# LED_Driver.net
KiCad netlist of a schematic drawn in Altium Designer
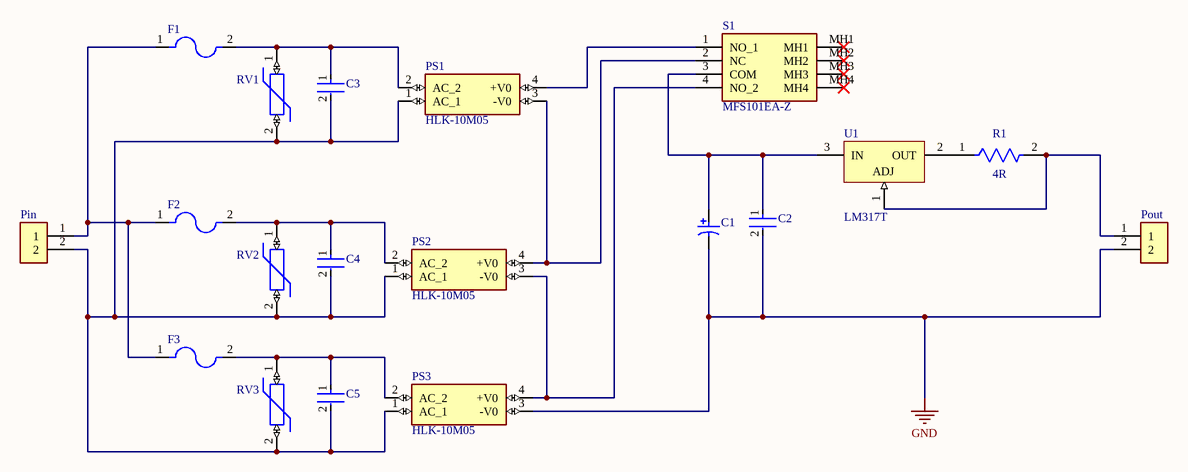
[diagram p0: LED_Driver.SchDoc]

(export (version "E")
  (design (tool "Eeschema 10.0.6"))
  (components
    (comp (ref "C1")
      (value "ECA-1VM221")
      (footprint "PNSC-ECA-1VM221-2")
      (description "Aluminum Electrolytic Capacitor, 220 uF, +/- 20%, 35 V, -40 to 85 degC, 2-Pin THD, RoHS, Bulk")
      (fields (field (name "MANUFACTURER") "Panasonic"))
      (libsource (lib "Altium Content Vault") (part "CAP-P-2"))
    )
    (comp (ref "C2")
      (value "C322C104K5R5TA")
      (footprint "FP-C322C104K5R5TA-MFG")
      (description "CAP CER 0.1UF 50V X7R RADIAL")
      (fields (field (name "TOLERANCE") "10%") (field (name "VOLTAGE") "50V"))
      (libsource (lib "Altium Content Vault") (part "b4654b650e69147ec39a6b967a45e02"))
    )
    (comp (ref "C3")
      (value "C322C104K5R5TA")
      (footprint "FP-C322C104K5R5TA-MFG")
      (description "CAP CER 0.1UF 50V X7R RADIAL")
      (fields (field (name "TOLERANCE") "10%") (field (name "VOLTAGE") "50V"))
      (libsource (lib "Altium Content Vault") (part "b4654b650e69147ec39a6b967a45e02"))
    )
    (comp (ref "C4")
      (value "C322C104K5R5TA")
      (footprint "FP-C322C104K5R5TA-MFG")
      (description "CAP CER 0.1UF 50V X7R RADIAL")
      (fields (field (name "TOLERANCE") "10%") (field (name "VOLTAGE") "50V"))
      (libsource (lib "Altium Content Vault") (part "b4654b650e69147ec39a6b967a45e02"))
    )
    (comp (ref "C5")
      (value "C322C104K5R5TA")
      (footprint "FP-C322C104K5R5TA-MFG")
      (description "CAP CER 0.1UF 50V X7R RADIAL")
      (fields (field (name "TOLERANCE") "10%") (field (name "VOLTAGE") "50V"))
      (libsource (lib "Altium Content Vault") (part "b4654b650e69147ec39a6b967a45e02"))
    )
    (comp (ref "F1")
      (value "5MFP-700-R")
      (footprint "FUSAD2668W81L2100D550")
      (description "5MFP 1-R (0651R1000-33) ¦ Glass Tube Fuse ¦ Axial Pigtail 5x20mm ¦ UL ¦ Fast Blow ¦ 1A")
      (libsource (lib "5MFP-700-R") (part "5MFP-700-R"))
    )
    (comp (ref "F2")
      (value "5MFP-700-R")
      (footprint "FUSAD2668W81L2100D550")
      (description "5MFP 1-R (0651R1000-33) ¦ Glass Tube Fuse ¦ Axial Pigtail 5x20mm ¦ UL ¦ Fast Blow ¦ 1A")
      (libsource (lib "5MFP-700-R") (part "5MFP-700-R"))
    )
    (comp (ref "F3")
      (value "5MFP-700-R")
      (footprint "FUSAD2668W81L2100D550")
      (description "5MFP 1-R (0651R1000-33) ¦ Glass Tube Fuse ¦ Axial Pigtail 5x20mm ¦ UL ¦ Fast Blow ¦ 1A")
      (libsource (lib "5MFP-700-R") (part "5MFP-700-R"))
    )
    (comp (ref "Pin")
      (value "282837-2")
      (footprint "TE_282837-2")
      (fields (field (name "MF") "TE Connectivity"))
      (libsource (lib "282837-2") (part "282837-2"))
    )
    (comp (ref "Pout")
      (value "282837-2")
      (footprint "TE_282837-2")
      (fields (field (name "MF") "TE Connectivity"))
      (libsource (lib "") (part "282837-2_1"))
    )
    (comp (ref "PS1")
      (value "HLK-10M05")
      (footprint "HLK10M05")
      (description "10W Ultra-Compact Power Module")
      (fields (field (name "MF") "Hi-link"))
      (libsource (lib "HLK-10M05") (part "HLK-10M05"))
    )
    (comp (ref "PS2")
      (value "HLK-10M05")
      (footprint "HLK10M05")
      (description "10W Ultra-Compact Power Module")
      (fields (field (name "MF") "Hi-link"))
      (libsource (lib "HLK-10M05") (part "HLK-10M05"))
    )
    (comp (ref "PS3")
      (value "HLK-10M05")
      (footprint "HLK10M05")
      (description "10W Ultra-Compact Power Module")
      (fields (field (name "MF") "Hi-link"))
      (libsource (lib "HLK-10M05") (part "HLK-10M05"))
    )
    (comp (ref "R1")
      (value "SP3AJT10R0")
      (footprint "FP-SP3A-MFG")
      (description "RES 10 OHM 5% 4W AXIAL")
      (fields (field (name "RESISTANCE") "4R") (field (name "TOLERANCE") "5%"))
      (libsource (lib "Altium Content Vault") (part "1029c3af85768c4190bb7ad29bc67b5"))
    )
    (comp (ref "RV1")
      (value "MOV-07D470K")
      (footprint "MOV-07DXXXK(3.9T)")
      (description "47 V 250 A Varistor 1 Circuit Through Hole Disc 7mm")
      (fields (field (name "MF") "Bourns"))
      (libsource (lib "MOV-07D470K") (part "MOV-07D470K"))
    )
    (comp (ref "RV2")
      (value "MOV-07D470K")
      (footprint "MOV-07DXXXK(3.9T)")
      (description "47 V 250 A Varistor 1 Circuit Through Hole Disc 7mm")
      (fields (field (name "MF") "Bourns"))
      (libsource (lib "MOV-07D470K") (part "MOV-07D470K"))
    )
    (comp (ref "RV3")
      (value "MOV-07D470K")
      (footprint "MOV-07DXXXK(3.9T)")
      (description "47 V 250 A Varistor 1 Circuit Through Hole Disc 7mm")
      (fields (field (name "MF") "Bourns"))
      (libsource (lib "MOV-07D470K") (part "MOV-07D470K"))
    )
    (comp (ref "S1")
      (value "MFS101EA-Z")
      (footprint "SamacSys:MFS101EAZ")
      (description "Switch")
      (fields (field (name "MOUSER PART NUMBER") "229-MFS101EA-Z"))
      (libsource (lib "*") (part "MFS101EA-Z"))
    )
    (comp (ref "U1")
      (value "LM317T")
      (footprint "TO-220")
      (description "1.5A, 1.2V to 37V Adjustable Voltage Regulator, 3-Pin TO-220")
      (libsource (lib "Altium Content Vault") (part "PM-REG-117-SIL3"))
    )
  )
  (nets
    (net (code "1") (name "GND") (class "Default")
      (node (ref "C1") (pin "2") (pinfunction "2_2") (pintype "passive"))
      (node (ref "C2") (pin "2") (pinfunction "2_2") (pintype "passive"))
      (node (ref "PS3") (pin "3") (pinfunction "-V0_3") (pintype "bidirectional"))
      (node (ref "Pout") (pin "2") (pinfunction "2_2") (pintype "passive"))
    )
    (net (code "2") (name "Net-(F1-Pad1)") (class "Default")
      (node (ref "F1") (pin "1") (pinfunction "1_1") (pintype "passive"))
      (node (ref "F2") (pin "1") (pinfunction "1_1") (pintype "passive"))
      (node (ref "F3") (pin "1") (pinfunction "1_1") (pintype "passive"))
      (node (ref "Pin") (pin "1") (pinfunction "1_1") (pintype "passive"))
    )
    (net (code "3") (name "Net-(PS1-+V0)") (class "Default")
      (node (ref "PS1") (pin "4") (pinfunction "+V0_4") (pintype "bidirectional"))
      (node (ref "S1") (pin "1") (pinfunction "NO_1_1") (pintype "passive"))
    )
    (net (code "4") (name "Net-(PS1--V0)") (class "Default")
      (node (ref "PS1") (pin "3") (pinfunction "-V0_3") (pintype "bidirectional"))
      (node (ref "PS2") (pin "4") (pinfunction "+V0_4") (pintype "bidirectional"))
      (node (ref "S1") (pin "2") (pinfunction "NC_2") (pintype "passive"))
    )
    (net (code "5") (name "Net-(PS1-AC_1)") (class "Default")
      (node (ref "C3") (pin "2") (pinfunction "2_2") (pintype "passive"))
      (node (ref "C4") (pin "2") (pinfunction "2_2") (pintype "passive"))
      (node (ref "C5") (pin "2") (pinfunction "2_2") (pintype "passive"))
      (node (ref "PS1") (pin "1") (pinfunction "AC_1_1") (pintype "bidirectional"))
      (node (ref "PS2") (pin "1") (pinfunction "AC_1_1") (pintype "bidirectional"))
      (node (ref "PS3") (pin "1") (pinfunction "AC_1_1") (pintype "bidirectional"))
      (node (ref "Pin") (pin "2") (pinfunction "2_2") (pintype "passive"))
      (node (ref "RV1") (pin "2") (pinfunction "2_2") (pintype "bidirectional"))
      (node (ref "RV2") (pin "2") (pinfunction "2_2") (pintype "bidirectional"))
      (node (ref "RV3") (pin "2") (pinfunction "2_2") (pintype "bidirectional"))
    )
    (net (code "6") (name "Net-(PS1-AC_2)") (class "Default")
      (node (ref "C3") (pin "1") (pinfunction "1_1") (pintype "passive"))
      (node (ref "F1") (pin "2") (pinfunction "2_2") (pintype "passive"))
      (node (ref "PS1") (pin "2") (pinfunction "AC_2_2") (pintype "bidirectional"))
      (node (ref "RV1") (pin "1") (pinfunction "1_1") (pintype "bidirectional"))
    )
    (net (code "7") (name "Net-(PS2--V0)") (class "Default")
      (node (ref "PS2") (pin "3") (pinfunction "-V0_3") (pintype "bidirectional"))
      (node (ref "PS3") (pin "4") (pinfunction "+V0_4") (pintype "bidirectional"))
      (node (ref "S1") (pin "4") (pinfunction "NO_2_4") (pintype "passive"))
    )
    (net (code "8") (name "Net-(PS2-AC_2)") (class "Default")
      (node (ref "C4") (pin "1") (pinfunction "1_1") (pintype "passive"))
      (node (ref "F2") (pin "2") (pinfunction "2_2") (pintype "passive"))
      (node (ref "PS2") (pin "2") (pinfunction "AC_2_2") (pintype "bidirectional"))
      (node (ref "RV2") (pin "1") (pinfunction "1_1") (pintype "bidirectional"))
    )
    (net (code "9") (name "Net-(PS3-AC_2)") (class "Default")
      (node (ref "C5") (pin "1") (pinfunction "1_1") (pintype "passive"))
      (node (ref "F3") (pin "2") (pinfunction "2_2") (pintype "passive"))
      (node (ref "PS3") (pin "2") (pinfunction "AC_2_2") (pintype "bidirectional"))
      (node (ref "RV3") (pin "1") (pinfunction "1_1") (pintype "bidirectional"))
    )
    (net (code "10") (name "Net-(S1-COM)") (class "Default")
      (node (ref "C1") (pin "1") (pinfunction "1_1") (pintype "passive"))
      (node (ref "C2") (pin "1") (pinfunction "1_1") (pintype "passive"))
      (node (ref "S1") (pin "3") (pinfunction "COM_3") (pintype "passive"))
      (node (ref "U1") (pin "3") (pinfunction "IN_3") (pintype "power_in"))
    )
    (net (code "11") (name "Net-(U1-ADJ)") (class "Default")
      (node (ref "Pout") (pin "1") (pinfunction "1_1") (pintype "passive"))
      (node (ref "R1") (pin "2") (pinfunction "2_2") (pintype "passive"))
      (node (ref "U1") (pin "1") (pinfunction "ADJ_1") (pintype "input"))
    )
    (net (code "12") (name "Net-(U1-OUT)") (class "Default")
      (node (ref "R1") (pin "1") (pinfunction "1_1") (pintype "passive"))
      (node (ref "U1") (pin "2") (pinfunction "OUT_2") (pintype "power_in"))
    )
    (net (code "13") (name "unconnected-(S1-PadMH1)") (class "Default")
      (node (ref "S1") (pin "MH1") (pinfunction "MH1_MH1") (pintype "passive+no_connect"))
    )
    (net (code "14") (name "unconnected-(S1-PadMH2)") (class "Default")
      (node (ref "S1") (pin "MH2") (pinfunction "MH2_MH2") (pintype "passive+no_connect"))
    )
    (net (code "15") (name "unconnected-(S1-PadMH3)") (class "Default")
      (node (ref "S1") (pin "MH3") (pinfunction "MH3_MH3") (pintype "passive+no_connect"))
    )
    (net (code "16") (name "unconnected-(S1-PadMH4)") (class "Default")
      (node (ref "S1") (pin "MH4") (pinfunction "MH4_MH4") (pintype "passive+no_connect"))
    )
  )
)
